# logic_conn.net
KiCad netlist of a schematic drawn in Altium Designer
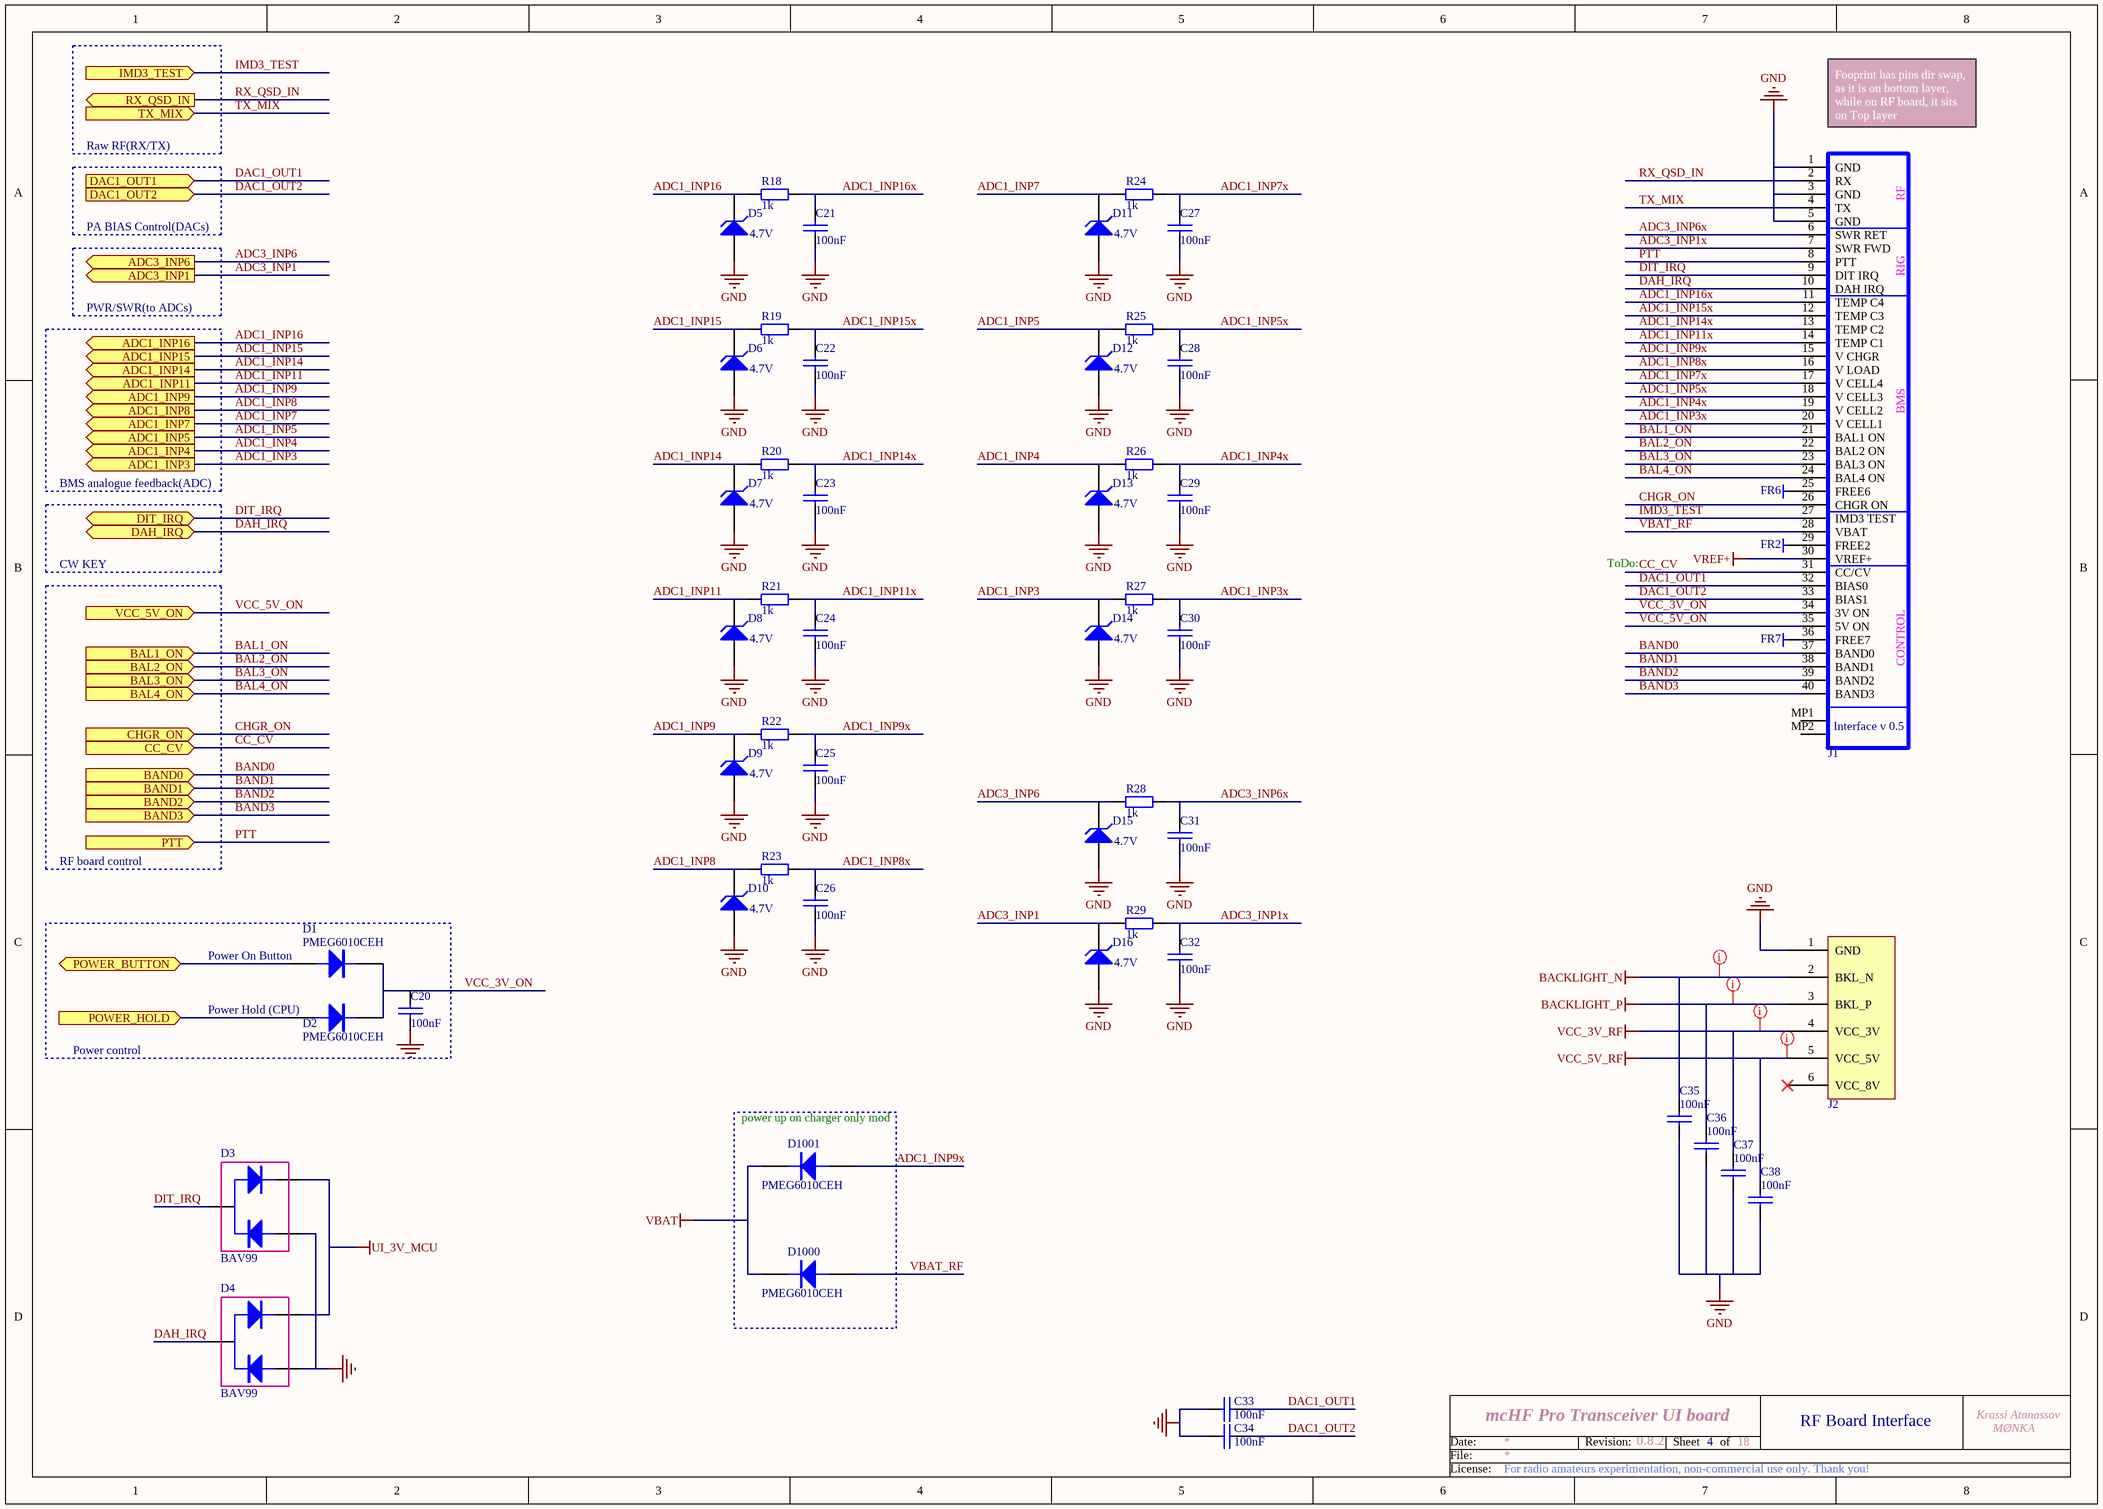
[diagram p0: logic_conn.SchDoc]

(export (version "E")
  (design (tool "Eeschema 10.0.6"))
  (components
    (comp (ref "C20")
      (value "100nF")
      (footprint "0805")
      (description "Capacitor")
      (libsource (lib "mcHF_ui") (part "CAP"))
    )
    (comp (ref "C21")
      (value "100nF")
      (footprint "0805")
      (description "Capacitor")
      (libsource (lib "mcHF_ui") (part "CAP"))
    )
    (comp (ref "C22")
      (value "100nF")
      (footprint "0805")
      (description "Capacitor")
      (libsource (lib "mcHF_ui") (part "CAP"))
    )
    (comp (ref "C23")
      (value "100nF")
      (footprint "0805")
      (description "Capacitor")
      (libsource (lib "mcHF_ui") (part "CAP"))
    )
    (comp (ref "C24")
      (value "100nF")
      (footprint "0805")
      (description "Capacitor")
      (libsource (lib "mcHF_ui") (part "CAP"))
    )
    (comp (ref "C25")
      (value "100nF")
      (footprint "0805")
      (description "Capacitor")
      (libsource (lib "mcHF_ui") (part "CAP"))
    )
    (comp (ref "C26")
      (value "100nF")
      (footprint "0805")
      (description "Capacitor")
      (libsource (lib "mcHF_ui") (part "CAP"))
    )
    (comp (ref "C27")
      (value "100nF")
      (footprint "0805")
      (description "Capacitor")
      (libsource (lib "mcHF_ui") (part "CAP"))
    )
    (comp (ref "C28")
      (value "100nF")
      (footprint "0805")
      (description "Capacitor")
      (libsource (lib "mcHF_ui") (part "CAP"))
    )
    (comp (ref "C29")
      (value "100nF")
      (footprint "0805")
      (description "Capacitor")
      (libsource (lib "mcHF_ui") (part "CAP"))
    )
    (comp (ref "C30")
      (value "100nF")
      (footprint "0805")
      (description "Capacitor")
      (libsource (lib "mcHF_ui") (part "CAP"))
    )
    (comp (ref "C31")
      (value "100nF")
      (footprint "0805")
      (description "Capacitor")
      (libsource (lib "mcHF_ui") (part "CAP"))
    )
    (comp (ref "C32")
      (value "100nF")
      (footprint "0805")
      (description "Capacitor")
      (libsource (lib "mcHF_ui") (part "CAP"))
    )
    (comp (ref "C33")
      (value "100nF")
      (footprint "0805")
      (description "Capacitor")
      (libsource (lib "mcHF_ui") (part "CAP"))
    )
    (comp (ref "C34")
      (value "100nF")
      (footprint "0805")
      (description "Capacitor")
      (libsource (lib "mcHF_ui") (part "CAP"))
    )
    (comp (ref "C35")
      (value "100nF")
      (footprint "0805")
      (description "Capacitor")
      (libsource (lib "mcHF_ui") (part "CAP"))
    )
    (comp (ref "C36")
      (value "100nF")
      (footprint "0805")
      (description "Capacitor")
      (libsource (lib "mcHF_ui") (part "CAP"))
    )
    (comp (ref "C37")
      (value "100nF")
      (footprint "0805")
      (description "Capacitor")
      (libsource (lib "mcHF_ui") (part "CAP"))
    )
    (comp (ref "C38")
      (value "100nF")
      (footprint "0805")
      (description "Capacitor")
      (libsource (lib "mcHF_ui") (part "CAP"))
    )
    (comp (ref "D1")
      (value "PMEG6010CEH")
      (footprint "SOD87")
      (description "DIODE, SCHOTTKY, 1A, 60V, SOD-123F")
      (libsource (lib "mcHF_rf") (part "PMEG6010CEH"))
    )
    (comp (ref "D2")
      (value "PMEG6010CEH")
      (footprint "SOD87")
      (description "DIODE, SCHOTTKY, 1A, 60V, SOD-123F")
      (libsource (lib "mcHF_rf") (part "PMEG6010CEH"))
    )
    (comp (ref "D3")
      (value "BAV99")
      (footprint "SOT-23")
      (description "Small Signal Diode, Dual Series")
      (libsource (lib "mcHF_rf") (part "BAV99"))
    )
    (comp (ref "D4")
      (value "BAV99")
      (footprint "SOT-23")
      (description "Small Signal Diode, Dual Series")
      (libsource (lib "mcHF_rf") (part "BAV99"))
    )
    (comp (ref "D5")
      (value "4.7V")
      (footprint "0805P")
      (description "Zener Diode")
      (fields (field (name "VOLTAGE") "4.5V - 5V") (field (name "PUBLISHER") "Altium Limited"))
      (libsource (lib "Miscellaneous Devices") (part "D Zener"))
    )
    (comp (ref "D6")
      (value "4.7V")
      (footprint "0805P")
      (description "Zener Diode")
      (fields (field (name "PUBLISHER") "Altium Limited"))
      (libsource (lib "Miscellaneous Devices") (part "D Zener"))
    )
    (comp (ref "D7")
      (value "4.7V")
      (footprint "0805P")
      (description "Zener Diode")
      (fields (field (name "PUBLISHER") "Altium Limited"))
      (libsource (lib "Miscellaneous Devices") (part "D Zener"))
    )
    (comp (ref "D8")
      (value "4.7V")
      (footprint "0805P")
      (description "Zener Diode")
      (fields (field (name "PUBLISHER") "Altium Limited"))
      (libsource (lib "Miscellaneous Devices") (part "D Zener"))
    )
    (comp (ref "D9")
      (value "4.7V")
      (footprint "0805P")
      (description "Zener Diode")
      (fields (field (name "PUBLISHER") "Altium Limited"))
      (libsource (lib "Miscellaneous Devices") (part "D Zener"))
    )
    (comp (ref "D10")
      (value "4.7V")
      (footprint "0805P")
      (description "Zener Diode")
      (fields (field (name "PUBLISHER") "Altium Limited"))
      (libsource (lib "Miscellaneous Devices") (part "D Zener"))
    )
    (comp (ref "D11")
      (value "4.7V")
      (footprint "0805P")
      (description "Zener Diode")
      (fields (field (name "PUBLISHER") "Altium Limited"))
      (libsource (lib "Miscellaneous Devices") (part "D Zener"))
    )
    (comp (ref "D12")
      (value "4.7V")
      (footprint "0805P")
      (description "Zener Diode")
      (fields (field (name "PUBLISHER") "Altium Limited"))
      (libsource (lib "Miscellaneous Devices") (part "D Zener"))
    )
    (comp (ref "D13")
      (value "4.7V")
      (footprint "0805P")
      (description "Zener Diode")
      (fields (field (name "PUBLISHER") "Altium Limited"))
      (libsource (lib "Miscellaneous Devices") (part "D Zener"))
    )
    (comp (ref "D14")
      (value "4.7V")
      (footprint "0805P")
      (description "Zener Diode")
      (fields (field (name "PUBLISHER") "Altium Limited"))
      (libsource (lib "Miscellaneous Devices") (part "D Zener"))
    )
    (comp (ref "D15")
      (value "4.7V")
      (footprint "0805P")
      (description "Zener Diode")
      (fields (field (name "PUBLISHER") "Altium Limited"))
      (libsource (lib "Miscellaneous Devices") (part "D Zener"))
    )
    (comp (ref "D16")
      (value "4.7V")
      (footprint "0805P")
      (description "Zener Diode")
      (fields (field (name "PUBLISHER") "Altium Limited"))
      (libsource (lib "Miscellaneous Devices") (part "D Zener"))
    )
    (comp (ref "D1000")
      (value "PMEG6010CEH")
      (footprint "SOD87")
      (description "DIODE, SCHOTTKY, 1A, 60V, SOD-123F")
      (libsource (lib "mcHF_rf") (part "PMEG6010CEH"))
    )
    (comp (ref "D1001")
      (value "PMEG6010CEH")
      (footprint "SOD87")
      (description "DIODE, SCHOTTKY, 1A, 60V, SOD-123F")
      (libsource (lib "mcHF_rf") (part "PMEG6010CEH"))
    )
    (comp (ref "FR2")
      (value "TP")
      (footprint "tp")
      (description "Test point")
      (libsource (lib "mcHF_ui_b") (part "TP"))
    )
    (comp (ref "FR6")
      (value "TP")
      (footprint "tp")
      (description "Test point")
      (libsource (lib "mcHF_ui_b") (part "TP"))
    )
    (comp (ref "FR7")
      (value "TP")
      (footprint "tp")
      (description "Test point")
      (libsource (lib "mcHF_ui_b") (part "TP"))
    )
    (comp (ref "J1")
      (value "INT V 0.5")
      (footprint "MOLX-54132-4033r")
      (description "40 pin FPC Flat cable connector, board to board")
      (libsource (lib "__ui") (part "PCB40_FLAT"))
    )
    (comp (ref "J2")
      (value "PWR6")
      (footprint "HDR_1x6_PWR_R")
      (description "Power connector")
      (libsource (lib "__ui") (part "PWR6"))
    )
    (comp (ref "R18")
      (value "1k")
      (footprint "0805")
      (description "Resistor")
      (libsource (lib "mcHF_ui") (part "RES"))
    )
    (comp (ref "R19")
      (value "1k")
      (footprint "0805")
      (description "Resistor")
      (libsource (lib "mcHF_ui") (part "RES"))
    )
    (comp (ref "R20")
      (value "1k")
      (footprint "0805")
      (description "Resistor")
      (libsource (lib "mcHF_ui") (part "RES"))
    )
    (comp (ref "R21")
      (value "1k")
      (footprint "0805")
      (description "Resistor")
      (libsource (lib "mcHF_ui") (part "RES"))
    )
    (comp (ref "R22")
      (value "1k")
      (footprint "0805")
      (description "Resistor")
      (libsource (lib "mcHF_ui") (part "RES"))
    )
    (comp (ref "R23")
      (value "1k")
      (footprint "0805")
      (description "Resistor")
      (libsource (lib "mcHF_ui") (part "RES"))
    )
    (comp (ref "R24")
      (value "1k")
      (footprint "0805")
      (description "Resistor")
      (libsource (lib "mcHF_ui") (part "RES"))
    )
    (comp (ref "R25")
      (value "1k")
      (footprint "0805")
      (description "Resistor")
      (libsource (lib "mcHF_ui") (part "RES"))
    )
    (comp (ref "R26")
      (value "1k")
      (footprint "0805")
      (description "Resistor")
      (libsource (lib "mcHF_ui") (part "RES"))
    )
    (comp (ref "R27")
      (value "1k")
      (footprint "0805")
      (description "Resistor")
      (libsource (lib "mcHF_ui") (part "RES"))
    )
    (comp (ref "R28")
      (value "1k")
      (footprint "0805")
      (description "Resistor")
      (libsource (lib "mcHF_ui") (part "RES"))
    )
    (comp (ref "R29")
      (value "1k")
      (footprint "0805")
      (description "Resistor")
      (libsource (lib "mcHF_ui") (part "RES"))
    )
  )
  (nets
    (net (code "1") (name "/ADC1_INP3") (class "Default")
      (node (ref "D14") (pin "2") (pinfunction "K_2") (pintype "passive"))
      (node (ref "R27") (pin "2") (pinfunction "2_2") (pintype "passive"))
    )
    (net (code "2") (name "/ADC1_INP3x") (class "Default")
      (node (ref "C30") (pin "2") (pinfunction "2_2") (pintype "passive"))
      (node (ref "J1") (pin "20") (pinfunction "V_CELL1_20") (pintype "passive"))
      (node (ref "R27") (pin "1") (pinfunction "1_1") (pintype "passive"))
    )
    (net (code "3") (name "/ADC1_INP4") (class "Default")
      (node (ref "D13") (pin "2") (pinfunction "K_2") (pintype "passive"))
      (node (ref "R26") (pin "2") (pinfunction "2_2") (pintype "passive"))
    )
    (net (code "4") (name "/ADC1_INP4x") (class "Default")
      (node (ref "C29") (pin "2") (pinfunction "2_2") (pintype "passive"))
      (node (ref "J1") (pin "19") (pinfunction "V_CELL2_19") (pintype "passive"))
      (node (ref "R26") (pin "1") (pinfunction "1_1") (pintype "passive"))
    )
    (net (code "5") (name "/ADC1_INP5") (class "Default")
      (node (ref "D12") (pin "2") (pinfunction "K_2") (pintype "passive"))
      (node (ref "R25") (pin "2") (pinfunction "2_2") (pintype "passive"))
    )
    (net (code "6") (name "/ADC1_INP5x") (class "Default")
      (node (ref "C28") (pin "2") (pinfunction "2_2") (pintype "passive"))
      (node (ref "J1") (pin "18") (pinfunction "V_CELL3_18") (pintype "passive"))
      (node (ref "R25") (pin "1") (pinfunction "1_1") (pintype "passive"))
    )
    (net (code "7") (name "/ADC1_INP7") (class "Default")
      (node (ref "D11") (pin "2") (pinfunction "K_2") (pintype "passive"))
      (node (ref "R24") (pin "2") (pinfunction "2_2") (pintype "passive"))
    )
    (net (code "8") (name "/ADC1_INP7x") (class "Default")
      (node (ref "C27") (pin "2") (pinfunction "2_2") (pintype "passive"))
      (node (ref "J1") (pin "17") (pinfunction "V_CELL4_17") (pintype "passive"))
      (node (ref "R24") (pin "1") (pinfunction "1_1") (pintype "passive"))
    )
    (net (code "9") (name "/ADC1_INP8") (class "Default")
      (node (ref "D10") (pin "2") (pinfunction "K_2") (pintype "passive"))
      (node (ref "R23") (pin "2") (pinfunction "2_2") (pintype "passive"))
    )
    (net (code "10") (name "/ADC1_INP8x") (class "Default")
      (node (ref "C26") (pin "2") (pinfunction "2_2") (pintype "passive"))
      (node (ref "J1") (pin "16") (pinfunction "V_LOAD_16") (pintype "passive"))
      (node (ref "R23") (pin "1") (pinfunction "1_1") (pintype "passive"))
    )
    (net (code "11") (name "/ADC1_INP9") (class "Default")
      (node (ref "D9") (pin "2") (pinfunction "K_2") (pintype "passive"))
      (node (ref "R22") (pin "2") (pinfunction "2_2") (pintype "passive"))
    )
    (net (code "12") (name "/ADC1_INP9x") (class "Default")
      (node (ref "C25") (pin "2") (pinfunction "2_2") (pintype "passive"))
      (node (ref "D1001") (pin "1") (pinfunction "A_1") (pintype "passive"))
      (node (ref "J1") (pin "15") (pinfunction "V_CHGR_15") (pintype "passive"))
      (node (ref "R22") (pin "1") (pinfunction "1_1") (pintype "passive"))
    )
    (net (code "13") (name "/ADC1_INP11") (class "Default")
      (node (ref "D8") (pin "2") (pinfunction "K_2") (pintype "passive"))
      (node (ref "R21") (pin "2") (pinfunction "2_2") (pintype "passive"))
    )
    (net (code "14") (name "/ADC1_INP11x") (class "Default")
      (node (ref "C24") (pin "2") (pinfunction "2_2") (pintype "passive"))
      (node (ref "J1") (pin "14") (pinfunction "TEMP_C1_14") (pintype "passive"))
      (node (ref "R21") (pin "1") (pinfunction "1_1") (pintype "passive"))
    )
    (net (code "15") (name "/ADC1_INP14") (class "Default")
      (node (ref "D7") (pin "2") (pinfunction "K_2") (pintype "passive"))
      (node (ref "R20") (pin "2") (pinfunction "2_2") (pintype "passive"))
    )
    (net (code "16") (name "/ADC1_INP14x") (class "Default")
      (node (ref "C23") (pin "2") (pinfunction "2_2") (pintype "passive"))
      (node (ref "J1") (pin "13") (pinfunction "TEMP_C2_13") (pintype "passive"))
      (node (ref "R20") (pin "1") (pinfunction "1_1") (pintype "passive"))
    )
    (net (code "17") (name "/ADC1_INP15") (class "Default")
      (node (ref "D6") (pin "2") (pinfunction "K_2") (pintype "passive"))
      (node (ref "R19") (pin "2") (pinfunction "2_2") (pintype "passive"))
    )
    (net (code "18") (name "/ADC1_INP15x") (class "Default")
      (node (ref "C22") (pin "2") (pinfunction "2_2") (pintype "passive"))
      (node (ref "J1") (pin "12") (pinfunction "TEMP_C3_12") (pintype "passive"))
      (node (ref "R19") (pin "1") (pinfunction "1_1") (pintype "passive"))
    )
    (net (code "19") (name "/ADC1_INP16") (class "Default")
      (node (ref "D5") (pin "2") (pinfunction "K_2") (pintype "passive"))
      (node (ref "R18") (pin "2") (pinfunction "2_2") (pintype "passive"))
    )
    (net (code "20") (name "/ADC1_INP16x") (class "Default")
      (node (ref "C21") (pin "2") (pinfunction "2_2") (pintype "passive"))
      (node (ref "J1") (pin "11") (pinfunction "TEMP_C4_11") (pintype "passive"))
      (node (ref "R18") (pin "1") (pinfunction "1_1") (pintype "passive"))
    )
    (net (code "21") (name "/ADC3_INP1") (class "Default")
      (node (ref "D16") (pin "2") (pinfunction "K_2") (pintype "passive"))
      (node (ref "R29") (pin "2") (pinfunction "2_2") (pintype "passive"))
    )
    (net (code "22") (name "/ADC3_INP1x") (class "Default")
      (node (ref "C32") (pin "2") (pinfunction "2_2") (pintype "passive"))
      (node (ref "J1") (pin "7") (pinfunction "SWR_FWD_7") (pintype "passive"))
      (node (ref "R29") (pin "1") (pinfunction "1_1") (pintype "passive"))
    )
    (net (code "23") (name "/ADC3_INP6") (class "Default")
      (node (ref "D15") (pin "2") (pinfunction "K_2") (pintype "passive"))
      (node (ref "R28") (pin "2") (pinfunction "2_2") (pintype "passive"))
    )
    (net (code "24") (name "/ADC3_INP6x") (class "Default")
      (node (ref "C31") (pin "2") (pinfunction "2_2") (pintype "passive"))
      (node (ref "J1") (pin "6") (pinfunction "SWR_RET_6") (pintype "passive"))
      (node (ref "R28") (pin "1") (pinfunction "1_1") (pintype "passive"))
    )
    (net (code "25") (name "/BAL1_ON") (class "Default")
      (node (ref "J1") (pin "21") (pinfunction "BAL1_ON_21") (pintype "passive"))
    )
    (net (code "26") (name "/BAL2_ON") (class "Default")
      (node (ref "J1") (pin "22") (pinfunction "BAL2_ON_22") (pintype "passive"))
    )
    (net (code "27") (name "/BAL3_ON") (class "Default")
      (node (ref "J1") (pin "23") (pinfunction "BAL3_ON_23") (pintype "passive"))
    )
    (net (code "28") (name "/BAL4_ON") (class "Default")
      (node (ref "J1") (pin "24") (pinfunction "BAL4_ON_24") (pintype "passive"))
    )
    (net (code "29") (name "/BAND0") (class "Default")
      (node (ref "J1") (pin "37") (pinfunction "BAND0_37") (pintype "passive"))
    )
    (net (code "30") (name "/BAND1") (class "Default")
      (node (ref "J1") (pin "38") (pinfunction "BAND1_38") (pintype "passive"))
    )
    (net (code "31") (name "/BAND2") (class "Default")
      (node (ref "J1") (pin "39") (pinfunction "BAND2_39") (pintype "passive"))
    )
    (net (code "32") (name "/BAND3") (class "Default")
      (node (ref "J1") (pin "40") (pinfunction "BAND3_40") (pintype "passive"))
    )
    (net (code "33") (name "/CC_CV") (class "Default")
      (node (ref "J1") (pin "31") (pinfunction "CC/CV_31") (pintype "passive"))
    )
    (net (code "34") (name "/CHGR_ON") (class "Default")
      (node (ref "J1") (pin "26") (pinfunction "CHGR_ON_26") (pintype "passive"))
    )
    (net (code "35") (name "/DAC1_OUT1") (class "Default")
      (node (ref "C33") (pin "1") (pinfunction "1_1") (pintype "passive"))
      (node (ref "J1") (pin "32") (pinfunction "BIAS0_32") (pintype "passive"))
    )
    (net (code "36") (name "/DAC1_OUT2") (class "Default")
      (node (ref "C34") (pin "1") (pinfunction "1_1") (pintype "passive"))
      (node (ref "J1") (pin "33") (pinfunction "BIAS1_33") (pintype "passive"))
    )
    (net (code "37") (name "/DAH_IRQ") (class "Default")
      (node (ref "D4") (pin "3") (pinfunction "C_3") (pintype "passive"))
      (node (ref "J1") (pin "10") (pinfunction "DAH_IRQ_10") (pintype "passive"))
    )
    (net (code "38") (name "/DIT_IRQ") (class "Default")
      (node (ref "D3") (pin "3") (pinfunction "C_3") (pintype "passive"))
      (node (ref "J1") (pin "9") (pinfunction "DIT_IRQ_9") (pintype "passive"))
    )
    (net (code "39") (name "/IMD3_TEST") (class "Default")
      (node (ref "J1") (pin "27") (pinfunction "IMD3_TEST_27") (pintype "passive"))
    )
    (net (code "40") (name "/POWER_BUTTON") (class "Default")
      (node (ref "D1") (pin "1") (pinfunction "A_1") (pintype "passive"))
    )
    (net (code "41") (name "/POWER_HOLD") (class "Default")
      (node (ref "D2") (pin "1") (pinfunction "A_1") (pintype "passive"))
    )
    (net (code "42") (name "/PTT") (class "Default")
      (node (ref "J1") (pin "8") (pinfunction "PTT_8") (pintype "passive"))
    )
    (net (code "43") (name "/RX_QSD_IN") (class "Default")
      (node (ref "J1") (pin "2") (pinfunction "RX_2") (pintype "passive"))
    )
    (net (code "44") (name "/TX_MIX") (class "Default")
      (node (ref "J1") (pin "4") (pinfunction "TX_4") (pintype "passive"))
    )
    (net (code "45") (name "/VBAT_RF") (class "Default")
      (node (ref "D1000") (pin "1") (pinfunction "A_1") (pintype "passive"))
      (node (ref "J1") (pin "28") (pinfunction "VBAT_28") (pintype "passive"))
    )
    (net (code "46") (name "/VCC_3V_ON") (class "Default")
      (node (ref "C20") (pin "2") (pinfunction "2_2") (pintype "passive"))
      (node (ref "D1") (pin "2") (pinfunction "K_2") (pintype "passive"))
      (node (ref "D2") (pin "2") (pinfunction "K_2") (pintype "passive"))
      (node (ref "J1") (pin "34") (pinfunction "3V_ON_34") (pintype "passive"))
    )
    (net (code "47") (name "/VCC_5V_ON") (class "Default")
      (node (ref "J1") (pin "35") (pinfunction "5V_ON_35") (pintype "passive"))
    )
    (net (code "48") (name "BACKLIGHT_N") (class "Default")
      (node (ref "C35") (pin "2") (pinfunction "2_2") (pintype "passive"))
      (node (ref "J2") (pin "2") (pinfunction "BKL_N_2") (pintype "passive"))
    )
    (net (code "49") (name "BACKLIGHT_P") (class "Default")
      (node (ref "C36") (pin "2") (pinfunction "2_2") (pintype "passive"))
      (node (ref "J2") (pin "3") (pinfunction "BKL_P_3") (pintype "passive"))
    )
    (net (code "50") (name "GND") (class "Default")
      (node (ref "C20") (pin "1") (pinfunction "1_1") (pintype "passive"))
      (node (ref "C21") (pin "1") (pinfunction "1_1") (pintype "passive"))
      (node (ref "C22") (pin "1") (pinfunction "1_1") (pintype "passive"))
      (node (ref "C23") (pin "1") (pinfunction "1_1") (pintype "passive"))
      (node (ref "C24") (pin "1") (pinfunction "1_1") (pintype "passive"))
      (node (ref "C25") (pin "1") (pinfunction "1_1") (pintype "passive"))
      (node (ref "C26") (pin "1") (pinfunction "1_1") (pintype "passive"))
      (node (ref "C27") (pin "1") (pinfunction "1_1") (pintype "passive"))
      (node (ref "C28") (pin "1") (pinfunction "1_1") (pintype "passive"))
      (node (ref "C29") (pin "1") (pinfunction "1_1") (pintype "passive"))
      (node (ref "C30") (pin "1") (pinfunction "1_1") (pintype "passive"))
      (node (ref "C31") (pin "1") (pinfunction "1_1") (pintype "passive"))
      (node (ref "C32") (pin "1") (pinfunction "1_1") (pintype "passive"))
      (node (ref "C33") (pin "2") (pinfunction "2_2") (pintype "passive"))
      (node (ref "C34") (pin "2") (pinfunction "2_2") (pintype "passive"))
      (node (ref "C35") (pin "1") (pinfunction "1_1") (pintype "passive"))
      (node (ref "C36") (pin "1") (pinfunction "1_1") (pintype "passive"))
      (node (ref "C37") (pin "1") (pinfunction "1_1") (pintype "passive"))
      (node (ref "C38") (pin "1") (pinfunction "1_1") (pintype "passive"))
      (node (ref "D10") (pin "1") (pinfunction "A_1") (pintype "passive"))
      (node (ref "D11") (pin "1") (pinfunction "A_1") (pintype "passive"))
      (node (ref "D12") (pin "1") (pinfunction "A_1") (pintype "passive"))
      (node (ref "D13") (pin "1") (pinfunction "A_1") (pintype "passive"))
      (node (ref "D14") (pin "1") (pinfunction "A_1") (pintype "passive"))
      (node (ref "D15") (pin "1") (pinfunction "A_1") (pintype "passive"))
      (node (ref "D16") (pin "1") (pinfunction "A_1") (pintype "passive"))
      (node (ref "D3") (pin "1") (pinfunction "A1_1") (pintype "passive"))
      (node (ref "D4") (pin "1") (pinfunction "A1_1") (pintype "passive"))
      (node (ref "D5") (pin "1") (pinfunction "A_1") (pintype "passive"))
      (node (ref "D6") (pin "1") (pinfunction "A_1") (pintype "passive"))
      (node (ref "D7") (pin "1") (pinfunction "A_1") (pintype "passive"))
      (node (ref "D8") (pin "1") (pinfunction "A_1") (pintype "passive"))
      (node (ref "D9") (pin "1") (pinfunction "A_1") (pintype "passive"))
      (node (ref "J1") (pin "1") (pinfunction "GND_1") (pintype "passive"))
      (node (ref "J1") (pin "3") (pinfunction "GND_3") (pintype "passive"))
      (node (ref "J1") (pin "5") (pinfunction "GND_5") (pintype "passive"))
      (node (ref "J2") (pin "1") (pinfunction "GND_1") (pintype "passive"))
    )
    (net (code "51") (name "Net-(J1-FREE2)") (class "Default")
      (node (ref "FR2") (pin "1") (pinfunction "1_1") (pintype "passive"))
      (node (ref "J1") (pin "29") (pinfunction "FREE2_29") (pintype "passive"))
    )
    (net (code "52") (name "Net-(J1-FREE6)") (class "Default")
      (node (ref "FR6") (pin "1") (pinfunction "1_1") (pintype "passive"))
      (node (ref "J1") (pin "25") (pinfunction "FREE6_25") (pintype "passive"))
    )
    (net (code "53") (name "Net-(J1-FREE7)") (class "Default")
      (node (ref "FR7") (pin "1") (pinfunction "1_1") (pintype "passive"))
      (node (ref "J1") (pin "36") (pinfunction "FREE7_36") (pintype "passive"))
    )
    (net (code "54") (name "UI_3V_MCU") (class "Default")
      (node (ref "D3") (pin "2") (pinfunction "K1_2") (pintype "passive"))
      (node (ref "D4") (pin "2") (pinfunction "K1_2") (pintype "passive"))
    )
    (net (code "55") (name "VBAT") (class "Default")
      (node (ref "D1000") (pin "2") (pinfunction "K_2") (pintype "passive"))
      (node (ref "D1001") (pin "2") (pinfunction "K_2") (pintype "passive"))
    )
    (net (code "56") (name "VCC_3V_RF") (class "Default")
      (node (ref "C37") (pin "2") (pinfunction "2_2") (pintype "passive"))
      (node (ref "J2") (pin "4") (pinfunction "VCC_3V_4") (pintype "passive"))
    )
    (net (code "57") (name "VCC_5V_RF") (class "Default")
      (node (ref "C38") (pin "2") (pinfunction "2_2") (pintype "passive"))
      (node (ref "J2") (pin "5") (pinfunction "VCC_5V_5") (pintype "passive"))
    )
    (net (code "58") (name "VREF+") (class "Default")
      (node (ref "J1") (pin "30") (pinfunction "VREF+_30") (pintype "passive"))
    )
    (net (code "59") (name "unconnected-(J1-PadMP1)") (class "Default")
      (node (ref "J1") (pin "MP1") (pinfunction "MP1_MP1") (pintype "passive"))
    )
    (net (code "60") (name "unconnected-(J1-PadMP2)") (class "Default")
      (node (ref "J1") (pin "MP2") (pinfunction "MP2_MP2") (pintype "passive"))
    )
    (net (code "61") (name "unconnected-(J2-VCC_8V-Pad6)") (class "Default")
      (node (ref "J2") (pin "6") (pinfunction "VCC_8V_6") (pintype "passive+no_connect"))
    )
  )
)
